# microSD_Shield-v13.net
KiCad netlist of a schematic drawn in EAGLE
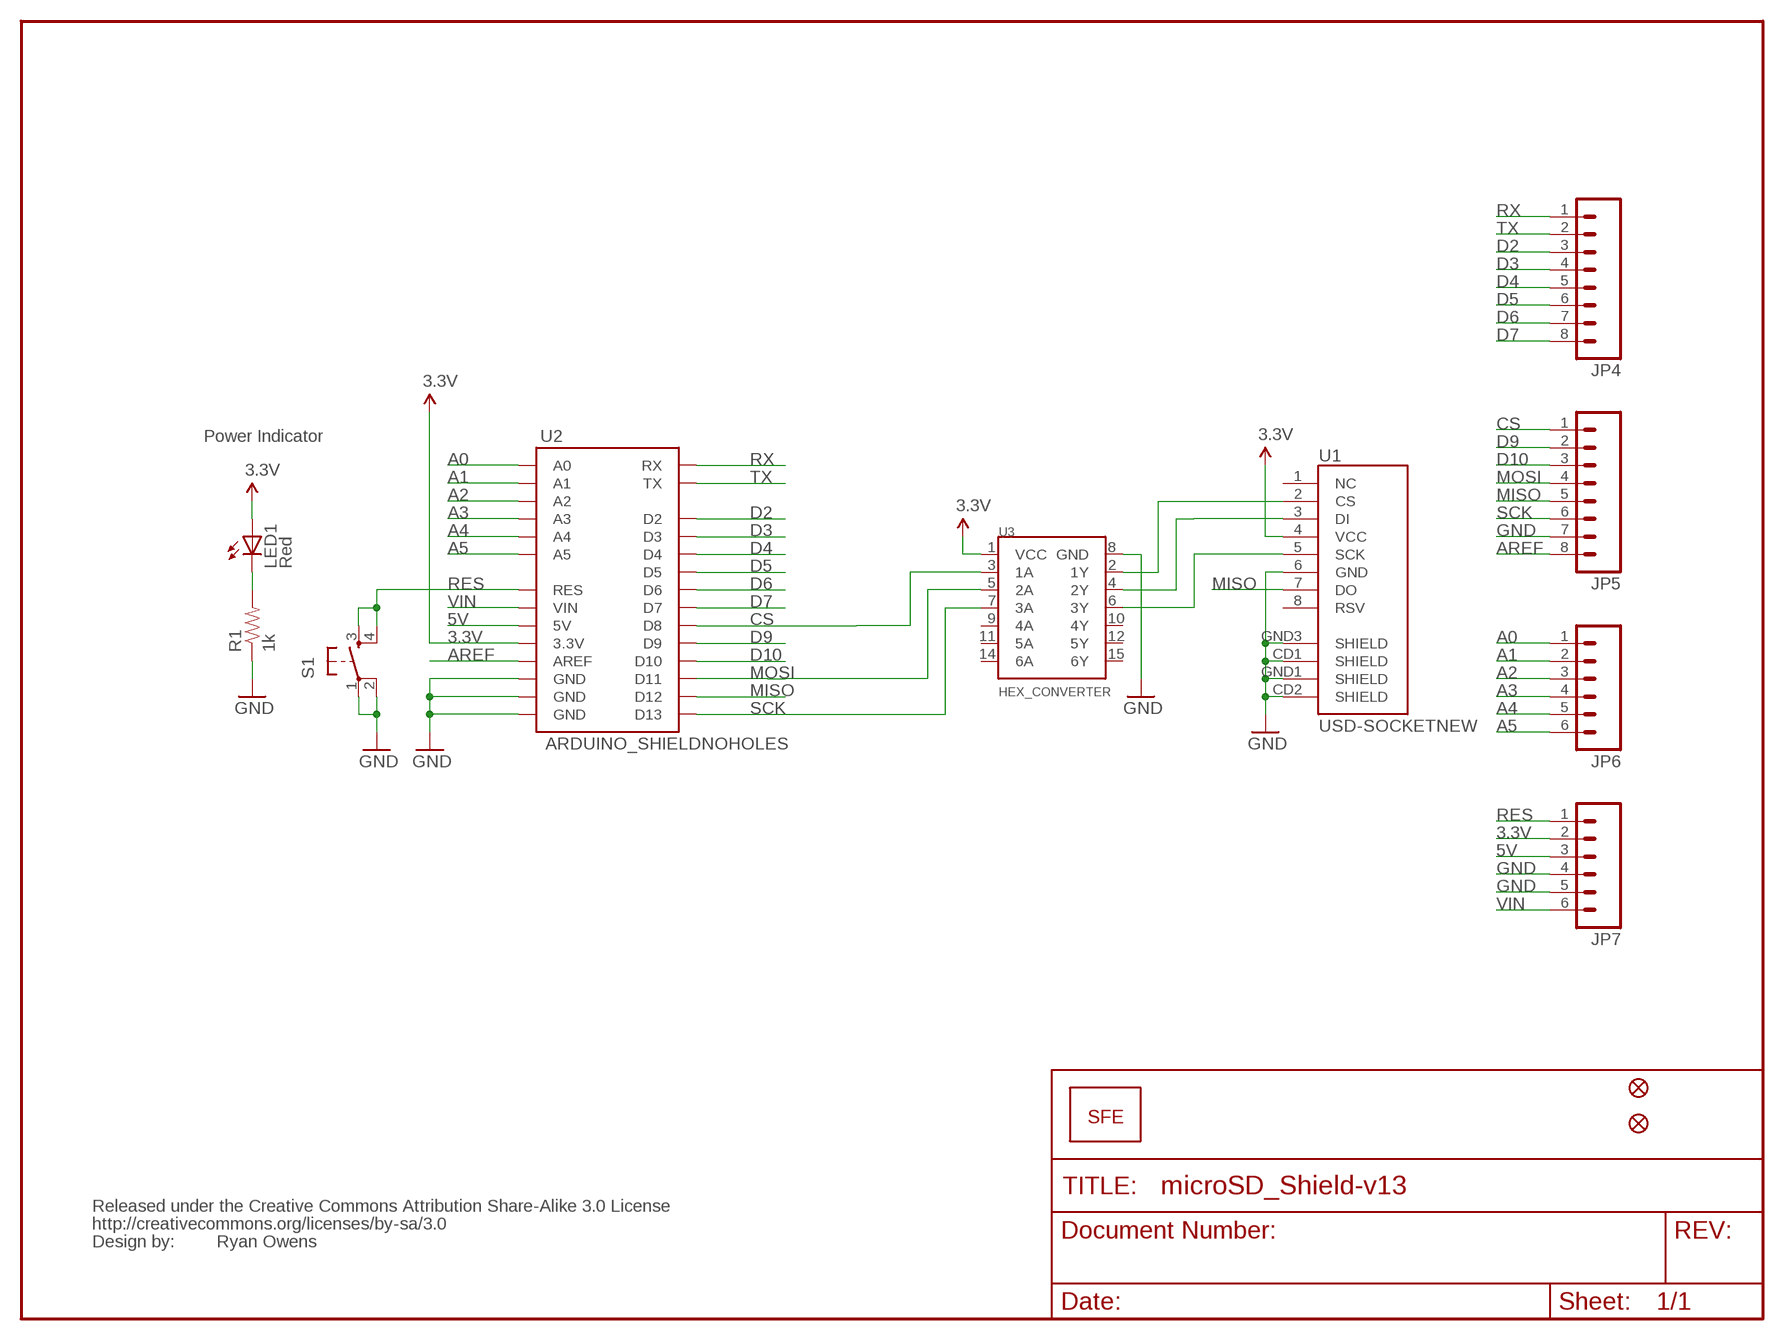
[diagram p0: schematic, sheet 1]

(export (version "E")
  (design (tool "Eeschema 10.0.6"))
  (components
    (comp (ref "JP1")
      (value "LOGO-SFENEW")
      (footprint "eagle-import:SFE-NEW-WEBLOGO")
      (libsource (lib "eagle-import") (part "LOGO-SFENEW"))
    )
    (comp (ref "JP2")
      (value "FIDUCIALUFIDUCIAL")
      (footprint "eagle-import:MICRO-FIDUCIAL")
      (libsource (lib "eagle-import") (part "FIDUCIALUFIDUCIAL"))
    )
    (comp (ref "JP3")
      (value "FIDUCIALUFIDUCIAL")
      (footprint "eagle-import:MICRO-FIDUCIAL")
      (libsource (lib "eagle-import") (part "FIDUCIALUFIDUCIAL"))
    )
    (comp (ref "JP4")
      (value "M08")
      (footprint "eagle-import:1X08")
      (libsource (lib "eagle-import") (part "M08"))
    )
    (comp (ref "JP5")
      (value "M08")
      (footprint "eagle-import:1X08")
      (libsource (lib "eagle-import") (part "M08"))
    )
    (comp (ref "JP6")
      (value "M06SIP")
      (footprint "eagle-import:1X06")
      (libsource (lib "eagle-import") (part "M06SIP"))
    )
    (comp (ref "JP7")
      (value "M06SIP")
      (footprint "eagle-import:1X06")
      (libsource (lib "eagle-import") (part "M06SIP"))
    )
    (comp (ref "LED1")
      (value "Red")
      (footprint "eagle-import:LED-0603")
      (libsource (lib "eagle-import") (part "LED0603"))
    )
    (comp (ref "R1")
      (value "1k")
      (footprint "eagle-import:0603-RES")
      (libsource (lib "eagle-import") (part "RESISTOR0603-RES"))
    )
    (comp (ref "S1")
      (value "TAC_SWITCHSMD")
      (footprint "eagle-import:TACTILE_SWITCH_SMD")
      (libsource (lib "eagle-import") (part "TAC_SWITCHSMD"))
    )
    (comp (ref "U$1")
      (value "CREATIVE_COMMONS")
      (footprint "eagle-import:CREATIVE_COMMONS")
      (libsource (lib "eagle-import") (part "CREATIVE_COMMONS"))
    )
    (comp (ref "U1")
      (value "USD-SOCKETNEW")
      (footprint "eagle-import:MICRO-SD-SOCKET-PP")
      (libsource (lib "eagle-import") (part "USD-SOCKETNEW"))
    )
    (comp (ref "U2")
      (value "ARDUINO_SHIELDNOHOLES")
      (footprint "eagle-import:DUEMILANOVE_SHIELD_NOHOLES")
      (libsource (lib "eagle-import") (part "ARDUINO_SHIELDNOHOLES"))
    )
    (comp (ref "U3")
      (value "HEX_CONVERTER")
      (footprint "eagle-import:SO016")
      (libsource (lib "eagle-import") (part "HEX_CONVERTER"))
    )
  )
  (nets
    (net (code "1") (name "/5V") (class "Default")
      (node (ref "JP7") (pin "3") (pinfunction "3_3") (pintype "passive"))
      (node (ref "U2") (pin "5V") (pinfunction "5V_5V") (pintype "bidirectional"))
    )
    (net (code "2") (name "/A0") (class "Default")
      (node (ref "JP6") (pin "1") (pinfunction "1_1") (pintype "passive"))
      (node (ref "U2") (pin "A0") (pinfunction "A0_A0") (pintype "bidirectional"))
    )
    (net (code "3") (name "/A1") (class "Default")
      (node (ref "JP6") (pin "2") (pinfunction "2_2") (pintype "passive"))
      (node (ref "U2") (pin "A1") (pinfunction "A1_A1") (pintype "bidirectional"))
    )
    (net (code "4") (name "/A2") (class "Default")
      (node (ref "JP6") (pin "3") (pinfunction "3_3") (pintype "passive"))
      (node (ref "U2") (pin "A2") (pinfunction "A2_A2") (pintype "bidirectional"))
    )
    (net (code "5") (name "/A3") (class "Default")
      (node (ref "JP6") (pin "4") (pinfunction "4_4") (pintype "passive"))
      (node (ref "U2") (pin "A3") (pinfunction "A3_A3") (pintype "bidirectional"))
    )
    (net (code "6") (name "/A4") (class "Default")
      (node (ref "JP6") (pin "5") (pinfunction "5_5") (pintype "passive"))
      (node (ref "U2") (pin "A4") (pinfunction "A4_A4") (pintype "bidirectional"))
    )
    (net (code "7") (name "/A5") (class "Default")
      (node (ref "JP6") (pin "6") (pinfunction "6_6") (pintype "passive"))
      (node (ref "U2") (pin "A5") (pinfunction "A5_A5") (pintype "bidirectional"))
    )
    (net (code "8") (name "/AREF") (class "Default")
      (node (ref "JP5") (pin "8") (pinfunction "8_8") (pintype "passive"))
      (node (ref "U2") (pin "AREF") (pinfunction "AREF_AREF") (pintype "bidirectional"))
    )
    (net (code "9") (name "/CS") (class "Default")
      (node (ref "JP5") (pin "1") (pinfunction "1_1") (pintype "passive"))
      (node (ref "U2") (pin "D8") (pinfunction "D8_D8") (pintype "bidirectional"))
      (node (ref "U3") (pin "3") (pinfunction "1A_3") (pintype "bidirectional"))
    )
    (net (code "10") (name "/D2") (class "Default")
      (node (ref "JP4") (pin "3") (pinfunction "3_3") (pintype "passive"))
      (node (ref "U2") (pin "D2") (pinfunction "D2_D2") (pintype "bidirectional"))
    )
    (net (code "11") (name "/D3") (class "Default")
      (node (ref "JP4") (pin "4") (pinfunction "4_4") (pintype "passive"))
      (node (ref "U2") (pin "D3") (pinfunction "D3_D3") (pintype "bidirectional"))
    )
    (net (code "12") (name "/D4") (class "Default")
      (node (ref "JP4") (pin "5") (pinfunction "5_5") (pintype "passive"))
      (node (ref "U2") (pin "D4") (pinfunction "D4_D4") (pintype "bidirectional"))
    )
    (net (code "13") (name "/D5") (class "Default")
      (node (ref "JP4") (pin "6") (pinfunction "6_6") (pintype "passive"))
      (node (ref "U2") (pin "D5") (pinfunction "D5_D5") (pintype "bidirectional"))
    )
    (net (code "14") (name "/D6") (class "Default")
      (node (ref "JP4") (pin "7") (pinfunction "7_7") (pintype "passive"))
      (node (ref "U2") (pin "D6") (pinfunction "D6_D6") (pintype "bidirectional"))
    )
    (net (code "15") (name "/D7") (class "Default")
      (node (ref "JP4") (pin "8") (pinfunction "8_8") (pintype "passive"))
      (node (ref "U2") (pin "D7") (pinfunction "D7_D7") (pintype "bidirectional"))
    )
    (net (code "16") (name "/D9") (class "Default")
      (node (ref "JP5") (pin "2") (pinfunction "2_2") (pintype "passive"))
      (node (ref "U2") (pin "D9") (pinfunction "D9_D9") (pintype "bidirectional"))
    )
    (net (code "17") (name "/D10") (class "Default")
      (node (ref "JP5") (pin "3") (pinfunction "3_3") (pintype "passive"))
      (node (ref "U2") (pin "D10") (pinfunction "D10_D10") (pintype "bidirectional"))
    )
    (net (code "18") (name "/MISO") (class "Default")
      (node (ref "JP5") (pin "5") (pinfunction "5_5") (pintype "passive"))
      (node (ref "U1") (pin "7") (pinfunction "DO_7") (pintype "bidirectional"))
      (node (ref "U2") (pin "D12") (pinfunction "D12_D12") (pintype "bidirectional"))
    )
    (net (code "19") (name "/MOSI") (class "Default")
      (node (ref "JP5") (pin "4") (pinfunction "4_4") (pintype "passive"))
      (node (ref "U2") (pin "D11") (pinfunction "D11_D11") (pintype "bidirectional"))
      (node (ref "U3") (pin "5") (pinfunction "2A_5") (pintype "bidirectional"))
    )
    (net (code "20") (name "/RES") (class "Default")
      (node (ref "JP7") (pin "1") (pinfunction "1_1") (pintype "passive"))
      (node (ref "S1") (pin "3") (pinfunction "3_3") (pintype "passive"))
      (node (ref "S1") (pin "4") (pinfunction "4_4") (pintype "passive"))
      (node (ref "U2") (pin "RES") (pinfunction "RES_RES") (pintype "bidirectional"))
    )
    (net (code "21") (name "/RX") (class "Default")
      (node (ref "JP4") (pin "1") (pinfunction "1_1") (pintype "passive"))
      (node (ref "U2") (pin "RX") (pinfunction "RX_RX") (pintype "bidirectional"))
    )
    (net (code "22") (name "/SCK") (class "Default")
      (node (ref "JP5") (pin "6") (pinfunction "6_6") (pintype "passive"))
      (node (ref "U2") (pin "D13") (pinfunction "D13_D13") (pintype "bidirectional"))
      (node (ref "U3") (pin "7") (pinfunction "3A_7") (pintype "bidirectional"))
    )
    (net (code "23") (name "/TX") (class "Default")
      (node (ref "JP4") (pin "2") (pinfunction "2_2") (pintype "passive"))
      (node (ref "U2") (pin "TX") (pinfunction "TX_TX") (pintype "bidirectional"))
    )
    (net (code "24") (name "/VIN") (class "Default")
      (node (ref "JP7") (pin "6") (pinfunction "6_6") (pintype "passive"))
      (node (ref "U2") (pin "VIN") (pinfunction "VIN_VIN") (pintype "bidirectional"))
    )
    (net (code "25") (name "3.3V") (class "Default")
      (node (ref "JP7") (pin "2") (pinfunction "2_2") (pintype "passive"))
      (node (ref "LED1") (pin "A") (pinfunction "A_A") (pintype "passive"))
      (node (ref "U1") (pin "4") (pinfunction "VCC_4") (pintype "bidirectional"))
      (node (ref "U2") (pin "3.3V") (pinfunction "3.3V_3.3V") (pintype "bidirectional"))
      (node (ref "U3") (pin "1") (pinfunction "VCC_1") (pintype "bidirectional"))
    )
    (net (code "26") (name "GND") (class "Default")
      (node (ref "JP5") (pin "7") (pinfunction "7_7") (pintype "passive"))
      (node (ref "JP7") (pin "4") (pinfunction "4_4") (pintype "passive"))
      (node (ref "JP7") (pin "5") (pinfunction "5_5") (pintype "passive"))
      (node (ref "R1") (pin "1") (pinfunction "1_1") (pintype "passive"))
      (node (ref "S1") (pin "1") (pinfunction "1_1") (pintype "passive"))
      (node (ref "S1") (pin "2") (pinfunction "2_2") (pintype "passive"))
      (node (ref "U1") (pin "6") (pinfunction "GND_6") (pintype "bidirectional"))
      (node (ref "U1") (pin "CD1") (pinfunction "SHIELD_CD1") (pintype "bidirectional"))
      (node (ref "U1") (pin "CD2") (pinfunction "SHIELD_CD2") (pintype "bidirectional"))
      (node (ref "U1") (pin "GND1") (pinfunction "SHIELD_GND1") (pintype "bidirectional"))
      (node (ref "U1") (pin "GND3") (pinfunction "SHIELD_GND3") (pintype "bidirectional"))
      (node (ref "U2") (pin "GND@0") (pinfunction "GND_GND@0") (pintype "bidirectional"))
      (node (ref "U2") (pin "GND@1") (pinfunction "GND_GND@1") (pintype "bidirectional"))
      (node (ref "U2") (pin "GND@2") (pinfunction "GND_GND@2") (pintype "bidirectional"))
      (node (ref "U3") (pin "8") (pinfunction "GND_8") (pintype "bidirectional"))
    )
    (net (code "27") (name "Net-(LED1-PadC)") (class "Default")
      (node (ref "LED1") (pin "C") (pinfunction "C_C") (pintype "passive"))
      (node (ref "R1") (pin "2") (pinfunction "2_2") (pintype "passive"))
    )
    (net (code "28") (name "Net-(U1-CS)") (class "Default")
      (node (ref "U1") (pin "2") (pinfunction "CS_2") (pintype "bidirectional"))
      (node (ref "U3") (pin "2") (pinfunction "1Y_2") (pintype "bidirectional"))
    )
    (net (code "29") (name "Net-(U1-DI)") (class "Default")
      (node (ref "U1") (pin "3") (pinfunction "DI_3") (pintype "bidirectional"))
      (node (ref "U3") (pin "4") (pinfunction "2Y_4") (pintype "bidirectional"))
    )
    (net (code "30") (name "Net-(U1-SCK)") (class "Default")
      (node (ref "U1") (pin "5") (pinfunction "SCK_5") (pintype "bidirectional"))
      (node (ref "U3") (pin "6") (pinfunction "3Y_6") (pintype "bidirectional"))
    )
    (net (code "31") (name "unconnected-(U1-NC-Pad1)") (class "Default")
      (node (ref "U1") (pin "1") (pinfunction "NC_1") (pintype "bidirectional"))
    )
    (net (code "32") (name "unconnected-(U1-RSV-Pad8)") (class "Default")
      (node (ref "U1") (pin "8") (pinfunction "RSV_8") (pintype "bidirectional"))
    )
    (net (code "33") (name "unconnected-(U3-4A-Pad9)") (class "Default")
      (node (ref "U3") (pin "9") (pinfunction "4A_9") (pintype "bidirectional"))
    )
    (net (code "34") (name "unconnected-(U3-4Y-Pad10)") (class "Default")
      (node (ref "U3") (pin "10") (pinfunction "4Y_10") (pintype "bidirectional"))
    )
    (net (code "35") (name "unconnected-(U3-5A-Pad11)") (class "Default")
      (node (ref "U3") (pin "11") (pinfunction "5A_11") (pintype "bidirectional"))
    )
    (net (code "36") (name "unconnected-(U3-5Y-Pad12)") (class "Default")
      (node (ref "U3") (pin "12") (pinfunction "5Y_12") (pintype "bidirectional"))
    )
    (net (code "37") (name "unconnected-(U3-6A-Pad14)") (class "Default")
      (node (ref "U3") (pin "14") (pinfunction "6A_14") (pintype "bidirectional"))
    )
    (net (code "38") (name "unconnected-(U3-6Y-Pad15)") (class "Default")
      (node (ref "U3") (pin "15") (pinfunction "6Y_15") (pintype "bidirectional"))
    )
  )
)
